# root.net
KiCad netlist of a schematic drawn in Altium Designer
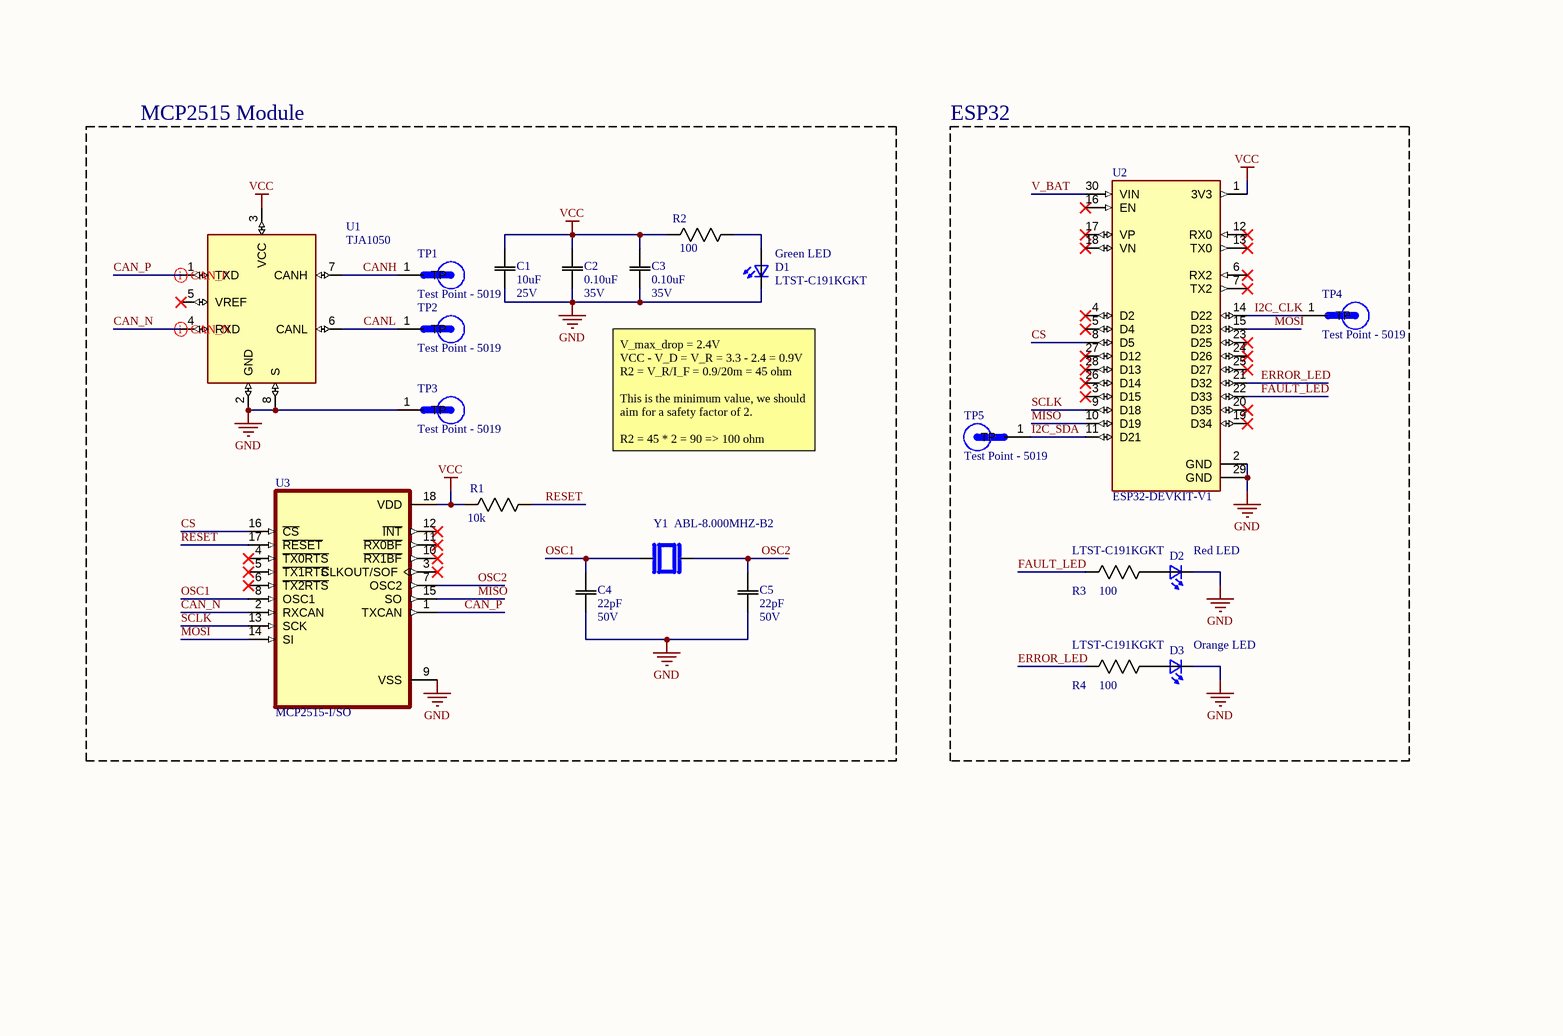
[diagram p0: root.SchDoc]

(export (version "E")
  (design (tool "Eeschema 10.0.6"))
  (components
    (comp (ref "C1")
      (value "10uF")
      (footprint "1206")
      (description "Default Symbol for Capacitors")
      (fields
        (field (name "RATING") "25V")
        (field (name "PART NUMBER") "CAP 10uF 25V")
        (field (name "TOLERANCE") "10%")
      )
      (libsource (lib "capacitor_library") (part "CAP_Default"))
    )
    (comp (ref "C2")
      (value "0.10uF")
      (footprint "0805")
      (description "CAP CER 0.10UF 35V X7R 0805")
      (fields
        (field (name "TOLERANCE") "10%")
        (field (name "RATING") "35V")
        (field (name "PART NUMBER") "CAP 0.10uF 35V")
      )
      (libsource (lib "capacitor_library") (part "CAP 0.10uF 35V"))
    )
    (comp (ref "C3")
      (value "0.10uF")
      (footprint "0805")
      (description "CAP CER 0.10UF 35V X7R 0805")
      (fields
        (field (name "TOLERANCE") "10%")
        (field (name "RATING") "35V")
        (field (name "PART NUMBER") "CAP 0.10uF 35V")
      )
      (libsource (lib "capacitor_library") (part "CAP 0.10uF 35V"))
    )
    (comp (ref "C4")
      (value "22pF")
      (footprint "0805")
      (description "Default Symbol for Capacitors")
      (fields
        (field (name "RATING") "50V")
        (field (name "PART NUMBER") "CAP 22pF 50V")
        (field (name "TOLERANCE") "10%")
      )
      (libsource (lib "capacitor_library") (part "CAP_Default"))
    )
    (comp (ref "C5")
      (value "22pF")
      (footprint "0805")
      (description "Default Symbol for Capacitors")
      (fields
        (field (name "RATING") "50V")
        (field (name "PART NUMBER") "CAP 22pF 50V")
        (field (name "TOLERANCE") "10%")
      )
      (libsource (lib "capacitor_library") (part "CAP_Default"))
    )
    (comp (ref "D1")
      (value "LTST-C191KGKT")
      (footprint "0603")
      (description "Green 571nm LED Indication - Discrete 2V 0603 (1608 Metric)")
      (fields (field (name "MF") "Lite-On Inc.") (field (name "DIGI-KEY_PART_NUMBER") "160-1446-2-ND"))
      (libsource (lib "LTST-C191KGKT") (part "LTST-C191KGKT"))
    )
    (comp (ref "D2")
      (value "LTST-C191KGKT")
      (footprint "0603")
      (description "Green 571nm LED Indication - Discrete 2V 0603 (1608 Metric)")
      (fields (field (name "MF") "Lite-On Inc.") (field (name "DIGI-KEY_PART_NUMBER") "160-1446-2-ND"))
      (libsource (lib "LTST-C191KGKT") (part "LTST-C191KGKT"))
    )
    (comp (ref "D3")
      (value "LTST-C191KGKT")
      (footprint "0603")
      (description "Green 571nm LED Indication - Discrete 2V 0603 (1608 Metric)")
      (fields (field (name "MF") "Lite-On Inc.") (field (name "DIGI-KEY_PART_NUMBER") "160-1446-2-ND"))
      (libsource (lib "LTST-C191KGKT") (part "LTST-C191KGKT"))
    )
    (comp (ref "R1")
      (value "10k")
      (footprint "0603")
      (description "RES SMD 10K OHM 1% 1/8W 0603")
      (fields (field (name "TOLERANCE") "5%") (field (name "PART NUMBER") "RES 10k 1/8W - 1%"))
      (libsource (lib "Resistor_Library") (part "RES 10k 1/8W 1%"))
    )
    (comp (ref "R2")
      (value "100")
      (footprint "0603")
      (description "Default Resistor Symbol")
      (fields (field (name "TOLERANCE") "5%") (field (name "PART NUMBER") "RES 100.0 1/8W - 5%"))
      (libsource (lib "") (part "RES_DEFAULT_1"))
    )
    (comp (ref "R3")
      (value "100")
      (footprint "0603")
      (description "Default Resistor Symbol")
      (fields (field (name "TOLERANCE") "5%") (field (name "PART NUMBER") "RES 100.0 1/8W - 5%"))
      (libsource (lib "") (part "RES_DEFAULT_1"))
    )
    (comp (ref "R4")
      (value "100")
      (footprint "0603")
      (description "Default Resistor Symbol")
      (fields (field (name "TOLERANCE") "5%") (field (name "PART NUMBER") "RES 100.0 1/8W - 5%"))
      (libsource (lib "Resistor_Library") (part "RES_DEFAULT"))
    )
    (comp (ref "TP1")
      (value "Test Point - 5019")
      (footprint "TP380X203")
      (description "PC Test Point, Miniature Phosphor Bronze, Silver Plating Surface Mount Mounting Type")
      (fields (field (name "MP") "5019") (field (name "MF") "Keystone Electronics"))
      (libsource (lib "IC_Library") (part "Test Point - 5019"))
    )
    (comp (ref "TP2")
      (value "Test Point - 5019")
      (footprint "TP380X203")
      (description "PC Test Point, Miniature Phosphor Bronze, Silver Plating Surface Mount Mounting Type")
      (fields (field (name "MP") "5019") (field (name "MF") "Keystone Electronics"))
      (libsource (lib "IC_Library") (part "Test Point - 5019"))
    )
    (comp (ref "TP3")
      (value "Test Point - 5019")
      (footprint "TP380X203")
      (description "PC Test Point, Miniature Phosphor Bronze, Silver Plating Surface Mount Mounting Type")
      (fields (field (name "MP") "5019") (field (name "MF") "Keystone Electronics"))
      (libsource (lib "IC_Library") (part "Test Point - 5019"))
    )
    (comp (ref "TP4")
      (value "Test Point - 5019")
      (footprint "TP380X203")
      (description "PC Test Point, Miniature Phosphor Bronze, Silver Plating Surface Mount Mounting Type")
      (fields (field (name "MP") "5019") (field (name "MF") "Keystone Electronics"))
      (libsource (lib "IC_Library") (part "Test Point - 5019"))
    )
    (comp (ref "TP5")
      (value "Test Point - 5019")
      (footprint "TP380X203")
      (description "PC Test Point, Miniature Phosphor Bronze, Silver Plating Surface Mount Mounting Type")
      (fields (field (name "MP") "5019") (field (name "MF") "Keystone Electronics"))
      (libsource (lib "IC_Library") (part "Test Point - 5019"))
    )
    (comp (ref "U1")
      (value "TJA1050")
      (footprint "SOP8")
      (description "1/1 Transceiver Half CANbus 8-SO")
      (fields (field (name "MF") "NXP USA"))
      (libsource (lib "TJA1050") (part "TJA1050"))
    )
    (comp (ref "U2")
      (value "ESP32-DEVKIT-V1")
      (footprint "MODULE_ESP32_DEVKIT_V1")
      (fields (field (name "MF") "Do it"))
      (libsource (lib "ESP32-DEVKIT-V1") (part "ESP32-DEVKIT-V1"))
    )
    (comp (ref "U3")
      (value "MCP2515-I/SO")
      (footprint "SOIC127P1030X265-18N")
      (description "CANbus Controller CAN 2.0 SPI Interface 18-SOIC")
      (fields (field (name "MF") "Microchip"))
      (libsource (lib "MCP2515-I_SO") (part "MCP2515-I/SO"))
    )
    (comp (ref "Y1")
      (value "ABL-8.000MHZ-B2")
      (footprint "XTAL_HC49P488W46L1150T500H350")
      (description "HC/49US (AT49) MICROPROCESSOR CRYSTAL")
      (fields (field (name "MF") "Abracon"))
      (libsource (lib "ABL-8.000MHZ-B2") (part "ABL-8.000MHZ-B2"))
    )
  )
  (nets
    (net (code "1") (name "/CANH") (class "Default")
      (node (ref "TP1") (pin "1") (pinfunction "TP_1") (pintype "passive"))
      (node (ref "U1") (pin "7") (pinfunction "CANH_7") (pintype "bidirectional"))
    )
    (net (code "2") (name "/CANL") (class "Default")
      (node (ref "TP2") (pin "1") (pinfunction "TP_1") (pintype "passive"))
      (node (ref "U1") (pin "6") (pinfunction "CANL_6") (pintype "bidirectional"))
    )
    (net (code "3") (name "/CAN_N") (class "Default")
      (node (ref "U1") (pin "4") (pinfunction "RXD_4") (pintype "bidirectional"))
      (node (ref "U3") (pin "2") (pinfunction "RXCAN_2") (pintype "input"))
    )
    (net (code "4") (name "/CAN_P") (class "Default")
      (node (ref "U1") (pin "1") (pinfunction "TXD_1") (pintype "bidirectional"))
      (node (ref "U3") (pin "1") (pinfunction "TXCAN_1") (pintype "output"))
    )
    (net (code "5") (name "/CS") (class "Default")
      (node (ref "U2") (pin "8") (pinfunction "D5_8") (pintype "bidirectional"))
      (node (ref "U3") (pin "16") (pinfunction "~{CS}_16") (pintype "input"))
    )
    (net (code "6") (name "/ERROR_LED") (class "Default")
      (node (ref "R4") (pin "2") (pinfunction "R2_2") (pintype "passive"))
      (node (ref "U2") (pin "21") (pinfunction "D32_21") (pintype "bidirectional"))
    )
    (net (code "7") (name "/FAULT_LED") (class "Default")
      (node (ref "R3") (pin "2") (pinfunction "R2_2") (pintype "passive"))
      (node (ref "U2") (pin "22") (pinfunction "D33_22") (pintype "bidirectional"))
    )
    (net (code "8") (name "/I2C_CLK") (class "Default")
      (node (ref "TP4") (pin "1") (pinfunction "TP_1") (pintype "passive"))
      (node (ref "U2") (pin "14") (pinfunction "D22_14") (pintype "bidirectional"))
    )
    (net (code "9") (name "/I2C_SDA") (class "Default")
      (node (ref "TP5") (pin "1") (pinfunction "TP_1") (pintype "passive"))
      (node (ref "U2") (pin "11") (pinfunction "D21_11") (pintype "bidirectional"))
    )
    (net (code "10") (name "/MISO") (class "Default")
      (node (ref "U2") (pin "10") (pinfunction "D19_10") (pintype "bidirectional"))
      (node (ref "U3") (pin "15") (pinfunction "SO_15") (pintype "output"))
    )
    (net (code "11") (name "/MOSI") (class "Default")
      (node (ref "U2") (pin "15") (pinfunction "D23_15") (pintype "bidirectional"))
      (node (ref "U3") (pin "14") (pinfunction "SI_14") (pintype "input"))
    )
    (net (code "12") (name "/OSC1") (class "Default")
      (node (ref "C4") (pin "2") (pinfunction "C2_2") (pintype "passive"))
      (node (ref "U3") (pin "8") (pinfunction "OSC1_8") (pintype "input"))
      (node (ref "Y1") (pin "1") (pinfunction "1_1") (pintype "passive"))
    )
    (net (code "13") (name "/OSC2") (class "Default")
      (node (ref "C5") (pin "2") (pinfunction "C2_2") (pintype "passive"))
      (node (ref "U3") (pin "7") (pinfunction "OSC2_7") (pintype "output"))
      (node (ref "Y1") (pin "2") (pinfunction "2_2") (pintype "passive"))
    )
    (net (code "14") (name "/RESET") (class "Default")
      (node (ref "R1") (pin "1") (pinfunction "R1_1") (pintype "passive"))
      (node (ref "U3") (pin "17") (pinfunction "~{RESET}_17") (pintype "input"))
    )
    (net (code "15") (name "/SCLK") (class "Default")
      (node (ref "U2") (pin "9") (pinfunction "D18_9") (pintype "bidirectional"))
      (node (ref "U3") (pin "13") (pinfunction "SCK_13") (pintype "input"))
    )
    (net (code "16") (name "/V_BAT") (class "Default")
      (node (ref "U2") (pin "30") (pinfunction "VIN_30") (pintype "input"))
    )
    (net (code "17") (name "GND") (class "Default")
      (node (ref "C1") (pin "1") (pinfunction "C1_1") (pintype "passive"))
      (node (ref "C2") (pin "1") (pinfunction "C1_1") (pintype "passive"))
      (node (ref "C3") (pin "1") (pinfunction "C1_1") (pintype "passive"))
      (node (ref "C4") (pin "1") (pinfunction "C1_1") (pintype "passive"))
      (node (ref "C5") (pin "1") (pinfunction "C1_1") (pintype "passive"))
      (node (ref "D1") (pin "1") (pinfunction "K2_1") (pintype "passive"))
      (node (ref "D2") (pin "1") (pinfunction "K2_1") (pintype "passive"))
      (node (ref "D3") (pin "1") (pinfunction "K2_1") (pintype "passive"))
      (node (ref "TP3") (pin "1") (pinfunction "TP_1") (pintype "passive"))
      (node (ref "U1") (pin "2") (pinfunction "GND_2") (pintype "bidirectional"))
      (node (ref "U1") (pin "8") (pinfunction "S_8") (pintype "bidirectional"))
      (node (ref "U2") (pin "2") (pinfunction "GND_2") (pintype "power_in"))
      (node (ref "U2") (pin "29") (pinfunction "GND_29") (pintype "power_in"))
      (node (ref "U3") (pin "9") (pinfunction "VSS_9") (pintype "power_in"))
    )
    (net (code "18") (name "Net-(D1-A2)") (class "Default")
      (node (ref "D1") (pin "2") (pinfunction "A2_2") (pintype "passive"))
      (node (ref "R2") (pin "1") (pinfunction "R1_1") (pintype "passive"))
    )
    (net (code "19") (name "Net-(D2-A2)") (class "Default")
      (node (ref "D2") (pin "2") (pinfunction "A2_2") (pintype "passive"))
      (node (ref "R3") (pin "1") (pinfunction "R1_1") (pintype "passive"))
    )
    (net (code "20") (name "Net-(D3-A2)") (class "Default")
      (node (ref "D3") (pin "2") (pinfunction "A2_2") (pintype "passive"))
      (node (ref "R4") (pin "1") (pinfunction "R1_1") (pintype "passive"))
    )
    (net (code "21") (name "VCC") (class "Default")
      (node (ref "C1") (pin "2") (pinfunction "C2_2") (pintype "passive"))
      (node (ref "C2") (pin "2") (pinfunction "C2_2") (pintype "passive"))
      (node (ref "C3") (pin "2") (pinfunction "C2_2") (pintype "passive"))
      (node (ref "R1") (pin "2") (pinfunction "R2_2") (pintype "passive"))
      (node (ref "R2") (pin "2") (pinfunction "R2_2") (pintype "passive"))
      (node (ref "U1") (pin "3") (pinfunction "VCC_3") (pintype "bidirectional"))
      (node (ref "U2") (pin "1") (pinfunction "3V3_1") (pintype "output"))
      (node (ref "U3") (pin "18") (pinfunction "VDD_18") (pintype "power_in"))
    )
    (net (code "22") (name "unconnected-(U1-VREF-Pad5)") (class "Default")
      (node (ref "U1") (pin "5") (pinfunction "VREF_5") (pintype "bidirectional+no_connect"))
    )
    (net (code "23") (name "unconnected-(U2-D2-Pad4)") (class "Default")
      (node (ref "U2") (pin "4") (pinfunction "D2_4") (pintype "bidirectional+no_connect"))
    )
    (net (code "24") (name "unconnected-(U2-D4-Pad5)") (class "Default")
      (node (ref "U2") (pin "5") (pinfunction "D4_5") (pintype "bidirectional+no_connect"))
    )
    (net (code "25") (name "unconnected-(U2-D12-Pad27)") (class "Default")
      (node (ref "U2") (pin "27") (pinfunction "D12_27") (pintype "bidirectional+no_connect"))
    )
    (net (code "26") (name "unconnected-(U2-D13-Pad28)") (class "Default")
      (node (ref "U2") (pin "28") (pinfunction "D13_28") (pintype "bidirectional+no_connect"))
    )
    (net (code "27") (name "unconnected-(U2-D14-Pad26)") (class "Default")
      (node (ref "U2") (pin "26") (pinfunction "D14_26") (pintype "bidirectional+no_connect"))
    )
    (net (code "28") (name "unconnected-(U2-D15-Pad3)") (class "Default")
      (node (ref "U2") (pin "3") (pinfunction "D15_3") (pintype "bidirectional+no_connect"))
    )
    (net (code "29") (name "unconnected-(U2-D25-Pad23)") (class "Default")
      (node (ref "U2") (pin "23") (pinfunction "D25_23") (pintype "bidirectional+no_connect"))
    )
    (net (code "30") (name "unconnected-(U2-D26-Pad24)") (class "Default")
      (node (ref "U2") (pin "24") (pinfunction "D26_24") (pintype "bidirectional+no_connect"))
    )
    (net (code "31") (name "unconnected-(U2-D27-Pad25)") (class "Default")
      (node (ref "U2") (pin "25") (pinfunction "D27_25") (pintype "bidirectional+no_connect"))
    )
    (net (code "32") (name "unconnected-(U2-D34-Pad19)") (class "Default")
      (node (ref "U2") (pin "19") (pinfunction "D34_19") (pintype "bidirectional+no_connect"))
    )
    (net (code "33") (name "unconnected-(U2-D35-Pad20)") (class "Default")
      (node (ref "U2") (pin "20") (pinfunction "D35_20") (pintype "bidirectional+no_connect"))
    )
    (net (code "34") (name "unconnected-(U2-EN-Pad16)") (class "Default")
      (node (ref "U2") (pin "16") (pinfunction "EN_16") (pintype "input+no_connect"))
    )
    (net (code "35") (name "unconnected-(U2-RX0-Pad12)") (class "Default")
      (node (ref "U2") (pin "12") (pinfunction "RX0_12") (pintype "input+no_connect"))
    )
    (net (code "36") (name "unconnected-(U2-RX2-Pad6)") (class "Default")
      (node (ref "U2") (pin "6") (pinfunction "RX2_6") (pintype "input+no_connect"))
    )
    (net (code "37") (name "unconnected-(U2-TX0-Pad13)") (class "Default")
      (node (ref "U2") (pin "13") (pinfunction "TX0_13") (pintype "output+no_connect"))
    )
    (net (code "38") (name "unconnected-(U2-TX2-Pad7)") (class "Default")
      (node (ref "U2") (pin "7") (pinfunction "TX2_7") (pintype "output+no_connect"))
    )
    (net (code "39") (name "unconnected-(U2-VN-Pad18)") (class "Default")
      (node (ref "U2") (pin "18") (pinfunction "VN_18") (pintype "bidirectional+no_connect"))
    )
    (net (code "40") (name "unconnected-(U2-VP-Pad17)") (class "Default")
      (node (ref "U2") (pin "17") (pinfunction "VP_17") (pintype "bidirectional+no_connect"))
    )
    (net (code "41") (name "unconnected-(U3-CLKOUT{slash}SOF-Pad3)") (class "Default")
      (node (ref "U3") (pin "3") (pinfunction "CLKOUT/SOF_3") (pintype "output+no_connect"))
    )
    (net (code "42") (name "unconnected-(U3-~{INT}-Pad12)") (class "Default")
      (node (ref "U3") (pin "12") (pinfunction "~{INT}_12") (pintype "output+no_connect"))
    )
    (net (code "43") (name "unconnected-(U3-~{RX0BF}-Pad11)") (class "Default")
      (node (ref "U3") (pin "11") (pinfunction "~{RX0BF}_11") (pintype "output+no_connect"))
    )
    (net (code "44") (name "unconnected-(U3-~{RX1BF}-Pad10)") (class "Default")
      (node (ref "U3") (pin "10") (pinfunction "~{RX1BF}_10") (pintype "output+no_connect"))
    )
    (net (code "45") (name "unconnected-(U3-~{TX0RTS}-Pad4)") (class "Default")
      (node (ref "U3") (pin "4") (pinfunction "~{TX0RTS}_4") (pintype "input+no_connect"))
    )
    (net (code "46") (name "unconnected-(U3-~{TX1RTS}-Pad5)") (class "Default")
      (node (ref "U3") (pin "5") (pinfunction "~{TX1RTS}_5") (pintype "input+no_connect"))
    )
    (net (code "47") (name "unconnected-(U3-~{TX2RTS}-Pad6)") (class "Default")
      (node (ref "U3") (pin "6") (pinfunction "~{TX2RTS}_6") (pintype "input+no_connect"))
    )
  )
)
